# 02_SETAB.net
KiCad netlist of a schematic drawn in EAGLE
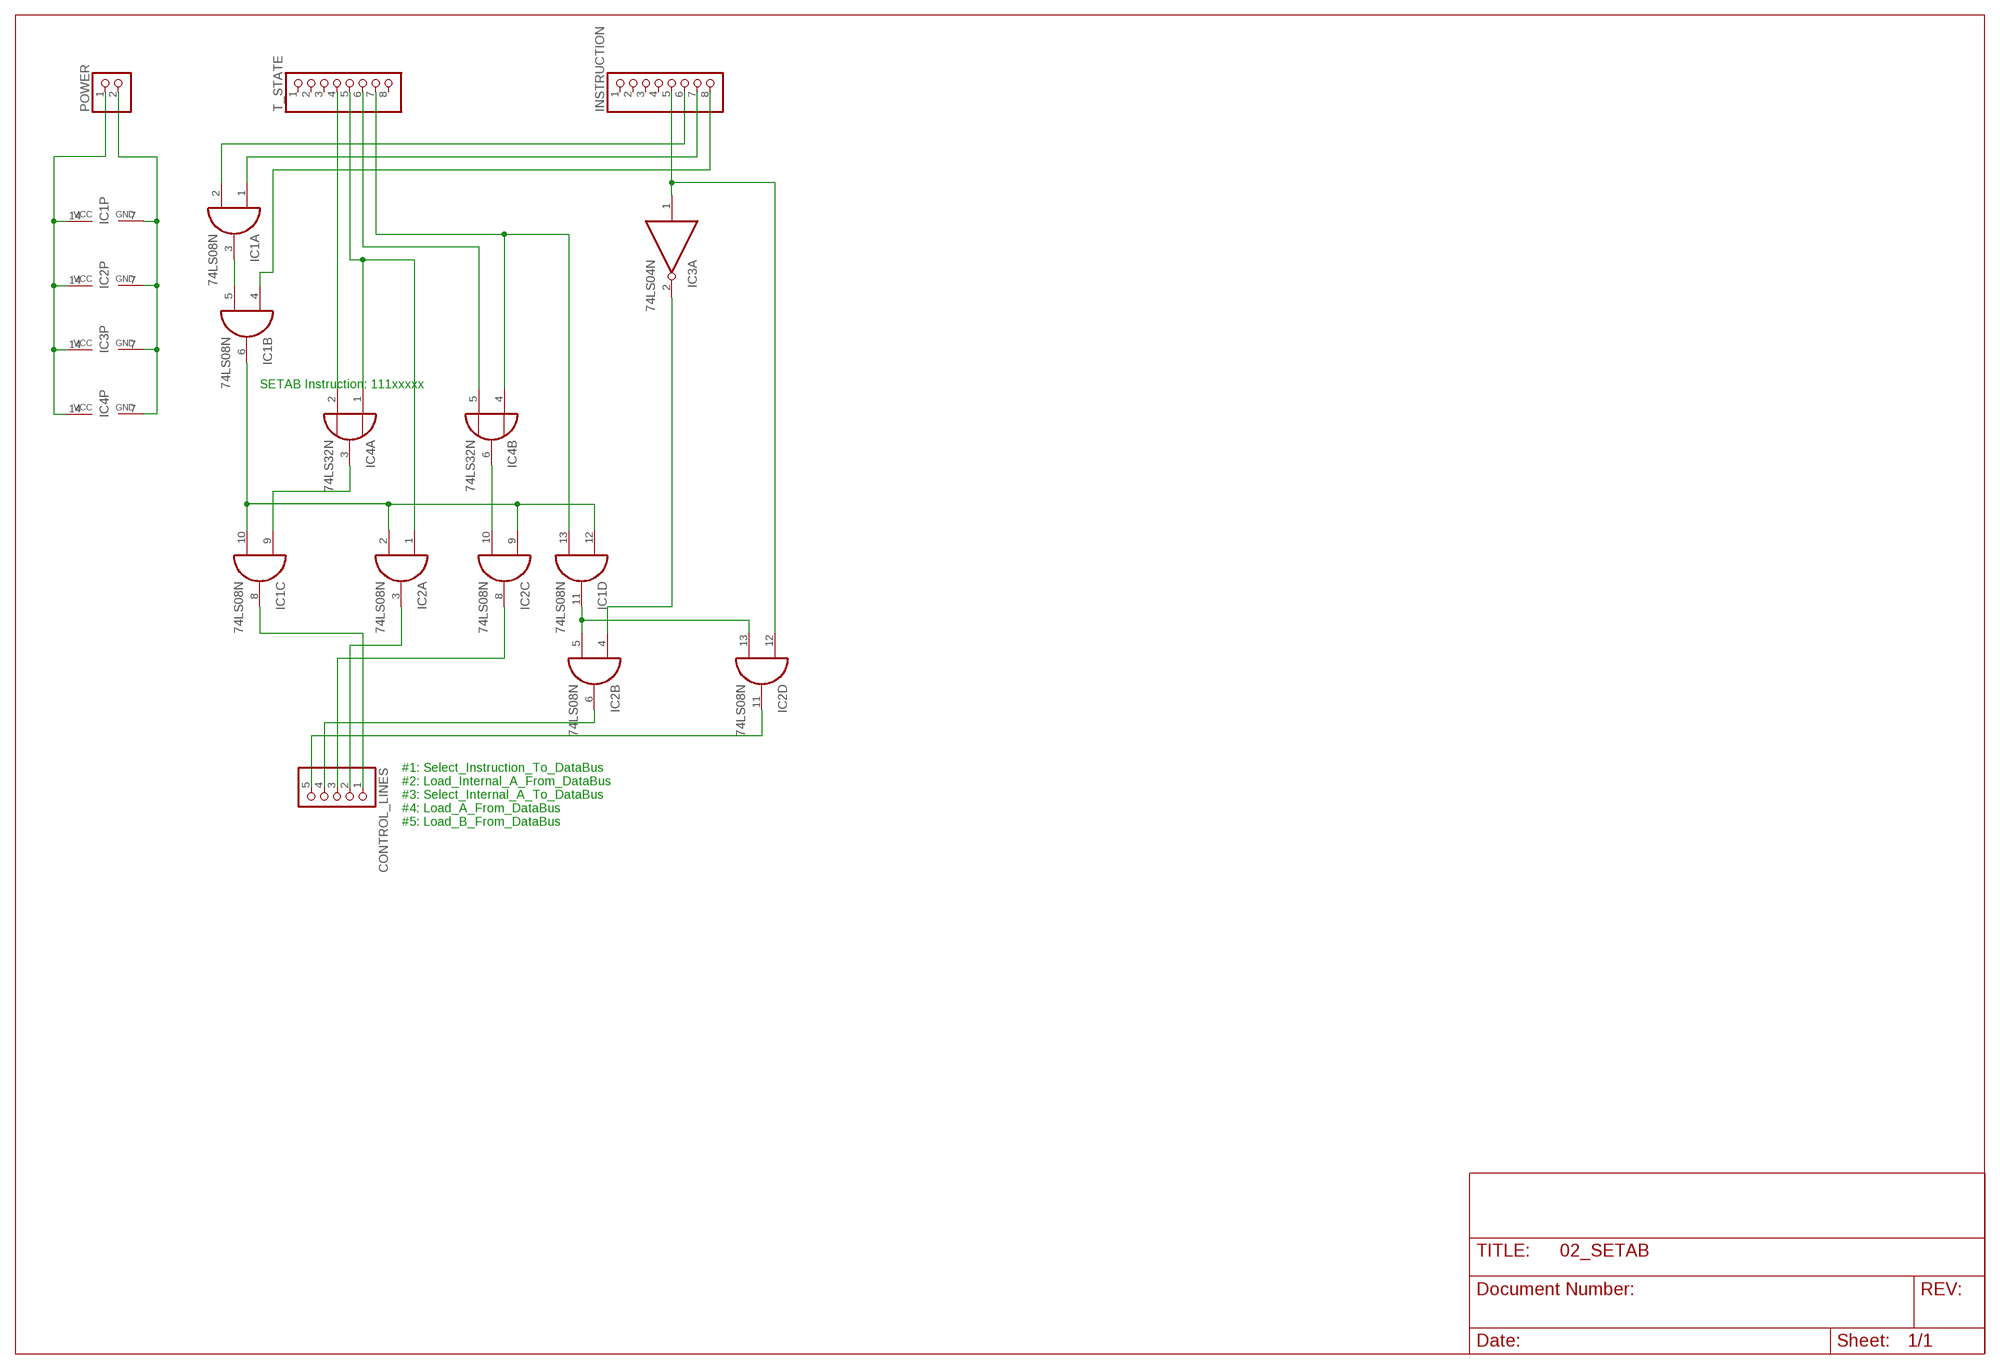
[diagram p0: schematic, sheet 1]

(export (version "E")
  (design (tool "Eeschema 10.0.6"))
  (components
    (comp (ref "CONTROL_LINES")
      (value "PINHD-1X5")
      (footprint "eagle-import:1X05")
      (libsource (lib "eagle-import") (part "PINHD-1X5"))
    )
    (comp (ref "IC1")
      (value "74LS08N")
      (footprint "eagle-import:DIL14")
      (libsource (lib "eagle-import") (part "7408NLS"))
    )
    (comp (ref "IC2")
      (value "74LS08N")
      (footprint "eagle-import:DIL14")
      (libsource (lib "eagle-import") (part "7408NLS"))
    )
    (comp (ref "IC3")
      (value "74LS04N")
      (footprint "eagle-import:DIL14")
      (libsource (lib "eagle-import") (part "7404NLS"))
    )
    (comp (ref "IC4")
      (value "74LS32N")
      (footprint "eagle-import:DIL14")
      (libsource (lib "eagle-import") (part "7432NLS"))
    )
    (comp (ref "INSTRUCTION")
      (value "PINHD-1X8")
      (footprint "eagle-import:1X08")
      (libsource (lib "eagle-import") (part "PINHD-1X8"))
    )
    (comp (ref "POWER")
      (value "PINHD-1X2")
      (footprint "eagle-import:1X02")
      (libsource (lib "eagle-import") (part "PINHD-1X2"))
    )
    (comp (ref "T_STATE")
      (value "PINHD-1X8")
      (footprint "eagle-import:1X08")
      (libsource (lib "eagle-import") (part "PINHD-1X8"))
    )
  )
  (nets
    (net (code "1") (name "Net-(IC1A-I0)") (class "Default")
      (node (ref "IC1") (pin "1") (pinfunction "I0_1") (pintype "input"))
      (node (ref "INSTRUCTION") (pin "7") (pinfunction "7_7") (pintype "passive"))
    )
    (net (code "2") (name "Net-(IC1A-I1)") (class "Default")
      (node (ref "IC1") (pin "2") (pinfunction "I1_2") (pintype "input"))
      (node (ref "INSTRUCTION") (pin "6") (pinfunction "6_6") (pintype "passive"))
    )
    (net (code "3") (name "Net-(IC1A-O)") (class "Default")
      (node (ref "IC1") (pin "3") (pinfunction "O_3") (pintype "output"))
      (node (ref "IC1") (pin "5") (pinfunction "I1_5") (pintype "input"))
    )
    (net (code "4") (name "Net-(IC1B-I0)") (class "Default")
      (node (ref "IC1") (pin "4") (pinfunction "I0_4") (pintype "input"))
      (node (ref "INSTRUCTION") (pin "8") (pinfunction "8_8") (pintype "passive"))
    )
    (net (code "5") (name "Net-(IC1B-O)") (class "Default")
      (node (ref "IC1") (pin "10") (pinfunction "I1_10") (pintype "input"))
      (node (ref "IC1") (pin "12") (pinfunction "I0_12") (pintype "input"))
      (node (ref "IC1") (pin "6") (pinfunction "O_6") (pintype "output"))
      (node (ref "IC2") (pin "2") (pinfunction "I1_2") (pintype "input"))
      (node (ref "IC2") (pin "9") (pinfunction "I0_9") (pintype "input"))
    )
    (net (code "6") (name "Net-(IC1C-I0)") (class "Default")
      (node (ref "IC1") (pin "9") (pinfunction "I0_9") (pintype "input"))
      (node (ref "IC4") (pin "3") (pinfunction "O_3") (pintype "output"))
    )
    (net (code "7") (name "Net-(IC1C-O)") (class "Default")
      (node (ref "CONTROL_LINES") (pin "1") (pinfunction "1_1") (pintype "passive"))
      (node (ref "IC1") (pin "8") (pinfunction "O_8") (pintype "output"))
    )
    (net (code "8") (name "Net-(IC1D-I1)") (class "Default")
      (node (ref "IC1") (pin "13") (pinfunction "I1_13") (pintype "input"))
      (node (ref "IC4") (pin "4") (pinfunction "I0_4") (pintype "input"))
      (node (ref "T_STATE") (pin "7") (pinfunction "7_7") (pintype "passive"))
    )
    (net (code "9") (name "Net-(IC1D-O)") (class "Default")
      (node (ref "IC1") (pin "11") (pinfunction "O_11") (pintype "output"))
      (node (ref "IC2") (pin "13") (pinfunction "I1_13") (pintype "input"))
      (node (ref "IC2") (pin "5") (pinfunction "I1_5") (pintype "input"))
    )
    (net (code "10") (name "Net-(IC1E-GND)") (class "Default")
      (node (ref "IC1") (pin "7") (pinfunction "GND_7") (pintype "power_in"))
      (node (ref "IC2") (pin "7") (pinfunction "GND_7") (pintype "power_in"))
      (node (ref "IC3") (pin "7") (pinfunction "GND_7") (pintype "power_in"))
      (node (ref "IC4") (pin "7") (pinfunction "GND_7") (pintype "power_in"))
      (node (ref "POWER") (pin "2") (pinfunction "2_2") (pintype "passive"))
    )
    (net (code "11") (name "Net-(IC1E-VCC)") (class "Default")
      (node (ref "IC1") (pin "14") (pinfunction "VCC_14") (pintype "power_in"))
      (node (ref "IC2") (pin "14") (pinfunction "VCC_14") (pintype "power_in"))
      (node (ref "IC3") (pin "14") (pinfunction "VCC_14") (pintype "power_in"))
      (node (ref "IC4") (pin "14") (pinfunction "VCC_14") (pintype "power_in"))
      (node (ref "POWER") (pin "1") (pinfunction "1_1") (pintype "passive"))
    )
    (net (code "12") (name "Net-(IC2A-I0)") (class "Default")
      (node (ref "IC2") (pin "1") (pinfunction "I0_1") (pintype "input"))
      (node (ref "IC4") (pin "1") (pinfunction "I0_1") (pintype "input"))
      (node (ref "T_STATE") (pin "5") (pinfunction "5_5") (pintype "passive"))
    )
    (net (code "13") (name "Net-(IC2A-O)") (class "Default")
      (node (ref "CONTROL_LINES") (pin "2") (pinfunction "2_2") (pintype "passive"))
      (node (ref "IC2") (pin "3") (pinfunction "O_3") (pintype "output"))
    )
    (net (code "14") (name "Net-(IC2B-I0)") (class "Default")
      (node (ref "IC2") (pin "4") (pinfunction "I0_4") (pintype "input"))
      (node (ref "IC3") (pin "2") (pinfunction "O_2") (pintype "output"))
    )
    (net (code "15") (name "Net-(IC2B-O)") (class "Default")
      (node (ref "CONTROL_LINES") (pin "4") (pinfunction "4_4") (pintype "passive"))
      (node (ref "IC2") (pin "6") (pinfunction "O_6") (pintype "output"))
    )
    (net (code "16") (name "Net-(IC2C-I1)") (class "Default")
      (node (ref "IC2") (pin "10") (pinfunction "I1_10") (pintype "input"))
      (node (ref "IC4") (pin "6") (pinfunction "O_6") (pintype "output"))
    )
    (net (code "17") (name "Net-(IC2C-O)") (class "Default")
      (node (ref "CONTROL_LINES") (pin "3") (pinfunction "3_3") (pintype "passive"))
      (node (ref "IC2") (pin "8") (pinfunction "O_8") (pintype "output"))
    )
    (net (code "18") (name "Net-(IC2D-I0)") (class "Default")
      (node (ref "IC2") (pin "12") (pinfunction "I0_12") (pintype "input"))
      (node (ref "IC3") (pin "1") (pinfunction "I_1") (pintype "input"))
      (node (ref "INSTRUCTION") (pin "5") (pinfunction "5_5") (pintype "passive"))
    )
    (net (code "19") (name "Net-(IC2D-O)") (class "Default")
      (node (ref "CONTROL_LINES") (pin "5") (pinfunction "5_5") (pintype "passive"))
      (node (ref "IC2") (pin "11") (pinfunction "O_11") (pintype "output"))
    )
    (net (code "20") (name "Net-(IC4A-I1)") (class "Default")
      (node (ref "IC4") (pin "2") (pinfunction "I1_2") (pintype "input"))
      (node (ref "T_STATE") (pin "4") (pinfunction "4_4") (pintype "passive"))
    )
    (net (code "21") (name "Net-(IC4B-I1)") (class "Default")
      (node (ref "IC4") (pin "5") (pinfunction "I1_5") (pintype "input"))
      (node (ref "T_STATE") (pin "6") (pinfunction "6_6") (pintype "passive"))
    )
    (net (code "22") (name "unconnected-(INSTRUCTION-Pad1)") (class "Default")
      (node (ref "INSTRUCTION") (pin "1") (pinfunction "1_1") (pintype "passive"))
    )
    (net (code "23") (name "unconnected-(INSTRUCTION-Pad2)") (class "Default")
      (node (ref "INSTRUCTION") (pin "2") (pinfunction "2_2") (pintype "passive"))
    )
    (net (code "24") (name "unconnected-(INSTRUCTION-Pad3)") (class "Default")
      (node (ref "INSTRUCTION") (pin "3") (pinfunction "3_3") (pintype "passive"))
    )
    (net (code "25") (name "unconnected-(INSTRUCTION-Pad4)") (class "Default")
      (node (ref "INSTRUCTION") (pin "4") (pinfunction "4_4") (pintype "passive"))
    )
    (net (code "26") (name "unconnected-(T_STATE-Pad1)") (class "Default")
      (node (ref "T_STATE") (pin "1") (pinfunction "1_1") (pintype "passive"))
    )
    (net (code "27") (name "unconnected-(T_STATE-Pad2)") (class "Default")
      (node (ref "T_STATE") (pin "2") (pinfunction "2_2") (pintype "passive"))
    )
    (net (code "28") (name "unconnected-(T_STATE-Pad3)") (class "Default")
      (node (ref "T_STATE") (pin "3") (pinfunction "3_3") (pintype "passive"))
    )
    (net (code "29") (name "unconnected-(T_STATE-Pad8)") (class "Default")
      (node (ref "T_STATE") (pin "8") (pinfunction "8_8") (pintype "passive"))
    )
  )
)
